# PCB1.net
KiCad netlist of a schematic drawn in Altium Designer
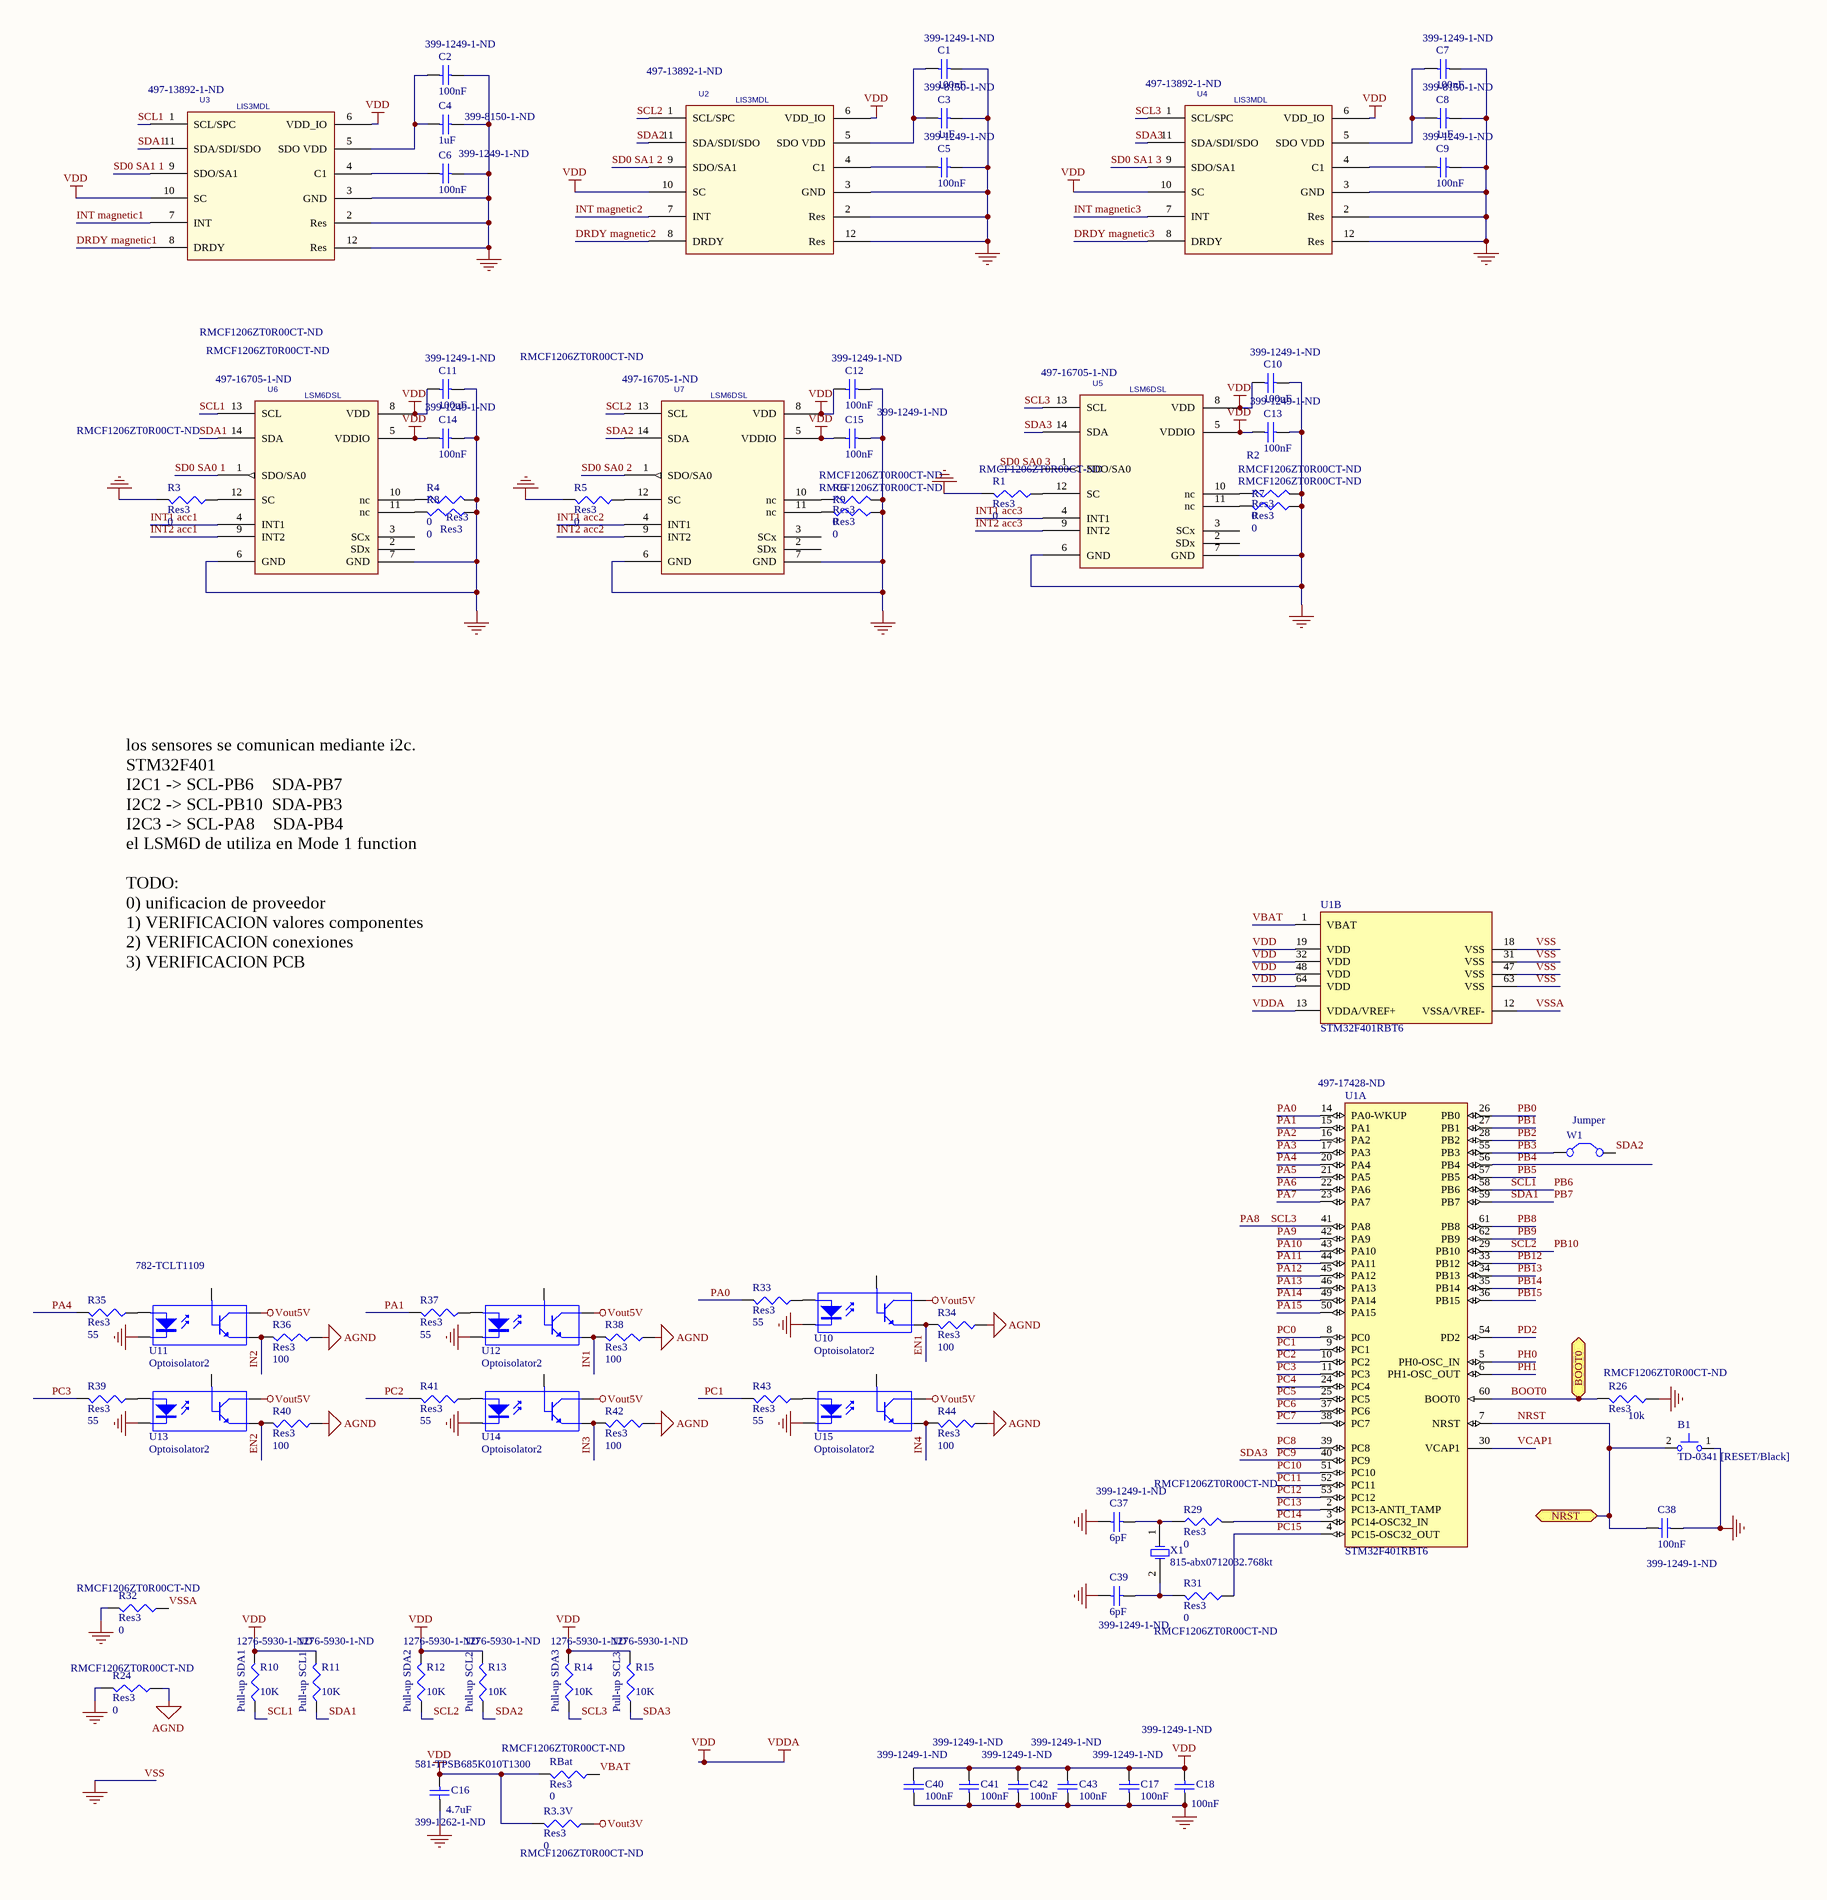
[diagram p0: PCB1.SchDoc, left]
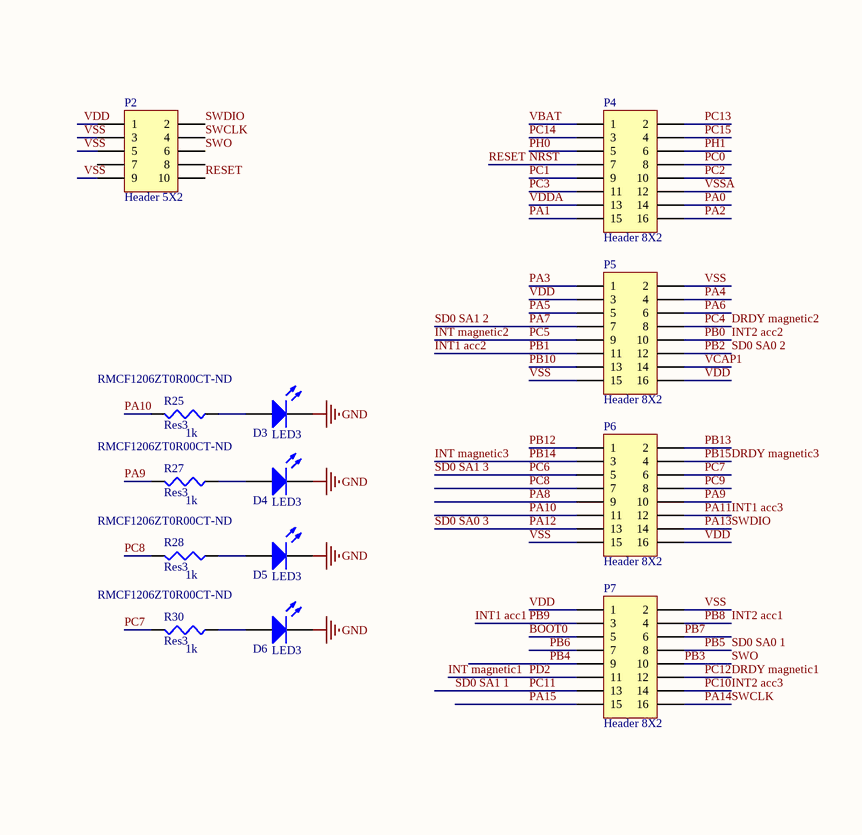
[diagram p1: PCB1.SchDoc, right]

(export (version "E")
  (design (tool "Eeschema 10.0.6"))
  (components
    (comp (ref "B1")
      (value "TD-0341 [RESET/Black]")
      (footprint "KSS-2G")
      (fields (field (name "PUBLISHER") "Altium Limited"))
      (libsource (lib "CK Switch") (part "KSS241GLFS"))
    )
    (comp (ref "C1")
      (value "100nF")
      (footprint "C1206")
      (description "Capacitor (Semiconductor SIM Model)")
      (fields
        (field (name "SUPPLIER PART NUMBER 1") "399-1249-1-ND")
        (field (name "Comment") "Cap Semi")
        (field (name "PUBLISHER") "Altium Limited")
      )
      (libsource (lib "Miscellaneous Devices") (part "Cap Semi"))
    )
    (comp (ref "C2")
      (value "100nF")
      (footprint "C1206")
      (description "Capacitor (Semiconductor SIM Model)")
      (fields
        (field (name "SUPPLIER PART NUMBER 1") "399-1249-1-ND")
        (field (name "Comment") "Cap Semi")
        (field (name "PUBLISHER") "Altium Limited")
      )
      (libsource (lib "Miscellaneous Devices") (part "Cap Semi"))
    )
    (comp (ref "C3")
      (value "1uF")
      (footprint "C1206")
      (description "Capacitor (Semiconductor SIM Model)")
      (fields
        (field (name "SUPPLIER PART NUMBER 1") "399-8150-1-ND")
        (field (name "Comment") "Cap Semi")
        (field (name "PUBLISHER") "Altium Limited")
      )
      (libsource (lib "Miscellaneous Devices") (part "Cap Semi"))
    )
    (comp (ref "C4")
      (value "1uF")
      (footprint "C1206")
      (description "Capacitor (Semiconductor SIM Model)")
      (fields
        (field (name "SUPPLIER PART NUMBER 1") "399-8150-1-ND")
        (field (name "Comment") "Cap Semi")
        (field (name "PUBLISHER") "Altium Limited")
      )
      (libsource (lib "Miscellaneous Devices") (part "Cap Semi"))
    )
    (comp (ref "C5")
      (value "100nF")
      (footprint "C1206")
      (description "Capacitor (Semiconductor SIM Model)")
      (fields
        (field (name "SUPPLIER PART NUMBER 1") "399-1249-1-ND")
        (field (name "Comment") "Cap Semi")
        (field (name "PUBLISHER") "Altium Limited")
      )
      (libsource (lib "Miscellaneous Devices") (part "Cap Semi"))
    )
    (comp (ref "C6")
      (value "100nF")
      (footprint "C1206")
      (description "Capacitor (Semiconductor SIM Model)")
      (fields
        (field (name "SUPPLIER PART NUMBER 1") "399-1249-1-ND")
        (field (name "Comment") "Cap Semi")
        (field (name "PUBLISHER") "Altium Limited")
      )
      (libsource (lib "Miscellaneous Devices") (part "Cap Semi"))
    )
    (comp (ref "C7")
      (value "100nF")
      (footprint "C1206")
      (description "Capacitor (Semiconductor SIM Model)")
      (fields
        (field (name "SUPPLIER PART NUMBER 1") "399-1249-1-ND")
        (field (name "Comment") "Cap Semi")
        (field (name "PUBLISHER") "Altium Limited")
      )
      (libsource (lib "Miscellaneous Devices") (part "Cap Semi"))
    )
    (comp (ref "C8")
      (value "1uF")
      (footprint "C1206")
      (description "Capacitor (Semiconductor SIM Model)")
      (fields
        (field (name "SUPPLIER PART NUMBER 1") "399-8150-1-ND")
        (field (name "Comment") "Cap Semi")
        (field (name "PUBLISHER") "Altium Limited")
      )
      (libsource (lib "Miscellaneous Devices") (part "Cap Semi"))
    )
    (comp (ref "C9")
      (value "100nF")
      (footprint "C1206")
      (description "Capacitor (Semiconductor SIM Model)")
      (fields
        (field (name "SUPPLIER PART NUMBER 1") "399-1249-1-ND")
        (field (name "Comment") "Cap Semi")
        (field (name "PUBLISHER") "Altium Limited")
      )
      (libsource (lib "Miscellaneous Devices") (part "Cap Semi"))
    )
    (comp (ref "C10")
      (value "100nF")
      (footprint "C1206")
      (description "Capacitor (Semiconductor SIM Model)")
      (fields
        (field (name "SUPPLIER PART NUMBER 1") "399-1249-1-ND")
        (field (name "Comment") "Cap Semi")
        (field (name "PUBLISHER") "Altium Limited")
      )
      (libsource (lib "Miscellaneous Devices") (part "Cap Semi"))
    )
    (comp (ref "C11")
      (value "100nF")
      (footprint "C1206")
      (description "Capacitor (Semiconductor SIM Model)")
      (fields
        (field (name "SUPPLIER PART NUMBER 1") "399-1249-1-ND")
        (field (name "Comment") "Cap Semi")
        (field (name "PUBLISHER") "Altium Limited")
      )
      (libsource (lib "Miscellaneous Devices") (part "Cap Semi"))
    )
    (comp (ref "C12")
      (value "100nF")
      (footprint "C1206")
      (description "Capacitor (Semiconductor SIM Model)")
      (fields
        (field (name "SUPPLIER PART NUMBER 1") "399-1249-1-ND")
        (field (name "Comment") "Cap Semi")
        (field (name "PUBLISHER") "Altium Limited")
      )
      (libsource (lib "Miscellaneous Devices") (part "Cap Semi"))
    )
    (comp (ref "C13")
      (value "100nF")
      (footprint "C1206")
      (description "Capacitor (Semiconductor SIM Model)")
      (fields
        (field (name "SUPPLIER PART NUMBER 1") "399-1249-1-ND")
        (field (name "Comment") "Cap Semi")
        (field (name "PUBLISHER") "Altium Limited")
      )
      (libsource (lib "Miscellaneous Devices") (part "Cap Semi"))
    )
    (comp (ref "C14")
      (value "100nF")
      (footprint "C1206")
      (description "Capacitor (Semiconductor SIM Model)")
      (fields
        (field (name "SUPPLIER PART NUMBER 1") "399-1249-1-ND")
        (field (name "Comment") "Cap Semi")
        (field (name "PUBLISHER") "Altium Limited")
      )
      (libsource (lib "Miscellaneous Devices") (part "Cap Semi"))
    )
    (comp (ref "C15")
      (value "100nF")
      (footprint "C1206")
      (description "Capacitor (Semiconductor SIM Model)")
      (fields
        (field (name "SUPPLIER PART NUMBER 1") "399-1249-1-ND")
        (field (name "Comment") "Cap Semi")
        (field (name "PUBLISHER") "Altium Limited")
      )
      (libsource (lib "Miscellaneous Devices") (part "Cap Semi"))
    )
    (comp (ref "C16")
      (value "4.7uF")
      (footprint "C1206")
      (description "Capacitor (Semiconductor SIM Model)")
      (fields
        (field (name "SUPPLIER PART NUMBER 1") "399-1262-1-ND")
        (field (name "SUPPLIER PART NUMBER 2") "581-TPSB685K010T1300")
        (field (name "Comment") "Cap Semi")
        (field (name "PUBLISHER") "Altium Limited")
      )
      (libsource (lib "Miscellaneous Devices") (part "Cap Semi"))
    )
    (comp (ref "C17")
      (value "100nF")
      (footprint "C1206")
      (description "Capacitor (Semiconductor SIM Model)")
      (fields
        (field (name "SUPPLIER PART NUMBER 1") "399-1249-1-ND")
        (field (name "Comment") "Cap Semi")
        (field (name "PUBLISHER") "Altium Limited")
      )
      (libsource (lib "Miscellaneous Devices") (part "Cap Semi"))
    )
    (comp (ref "C18")
      (value "100nF")
      (footprint "C1206")
      (description "Capacitor (Semiconductor SIM Model)")
      (fields
        (field (name "SUPPLIER PART NUMBER 1") "399-1249-1-ND")
        (field (name "Comment") "Cap Semi")
        (field (name "PUBLISHER") "Altium Limited")
      )
      (libsource (lib "Miscellaneous Devices") (part "Cap Semi"))
    )
    (comp (ref "C37")
      (value "6pF")
      (footprint "C1206")
      (description "Capacitor (Semiconductor SIM Model)")
      (fields
        (field (name "SUPPLIER PART NUMBER 1") "399-1249-1-ND")
        (field (name "Comment") "Cap Semi")
        (field (name "PUBLISHER") "Altium Limited")
      )
      (libsource (lib "Miscellaneous Devices") (part "Cap Semi"))
    )
    (comp (ref "C38")
      (value "100nF")
      (footprint "C1206")
      (description "Capacitor (Semiconductor SIM Model)")
      (fields
        (field (name "SUPPLIER PART NUMBER 1") "399-1249-1-ND")
        (field (name "Comment") "Cap Semi")
        (field (name "PUBLISHER") "Altium Limited")
      )
      (libsource (lib "Miscellaneous Devices") (part "Cap Semi"))
    )
    (comp (ref "C39")
      (value "6pF")
      (footprint "C1206")
      (description "Capacitor (Semiconductor SIM Model)")
      (fields
        (field (name "SUPPLIER PART NUMBER 1") "399-1249-1-ND")
        (field (name "Comment") "Cap Semi")
        (field (name "PUBLISHER") "Altium Limited")
      )
      (libsource (lib "Miscellaneous Devices") (part "Cap Semi"))
    )
    (comp (ref "C40")
      (value "100nF")
      (footprint "C1206")
      (description "Capacitor (Semiconductor SIM Model)")
      (fields
        (field (name "SUPPLIER PART NUMBER 1") "399-1249-1-ND")
        (field (name "Comment") "Cap Semi")
        (field (name "PUBLISHER") "Altium Limited")
      )
      (libsource (lib "Miscellaneous Devices") (part "Cap Semi"))
    )
    (comp (ref "C41")
      (value "100nF")
      (footprint "C1206")
      (description "Capacitor (Semiconductor SIM Model)")
      (fields
        (field (name "SUPPLIER PART NUMBER 1") "399-1249-1-ND")
        (field (name "Comment") "Cap Semi")
        (field (name "PUBLISHER") "Altium Limited")
      )
      (libsource (lib "Miscellaneous Devices") (part "Cap Semi"))
    )
    (comp (ref "C42")
      (value "100nF")
      (footprint "C1206")
      (description "Capacitor (Semiconductor SIM Model)")
      (fields
        (field (name "SUPPLIER PART NUMBER 1") "399-1249-1-ND")
        (field (name "Comment") "Cap Semi")
        (field (name "PUBLISHER") "Altium Limited")
      )
      (libsource (lib "Miscellaneous Devices") (part "Cap Semi"))
    )
    (comp (ref "C43")
      (value "100nF")
      (footprint "C1206")
      (description "Capacitor (Semiconductor SIM Model)")
      (fields
        (field (name "SUPPLIER PART NUMBER 1") "399-1249-1-ND")
        (field (name "Comment") "Cap Semi")
        (field (name "PUBLISHER") "Altium Limited")
      )
      (libsource (lib "Miscellaneous Devices") (part "Cap Semi"))
    )
    (comp (ref "D3")
      (value "LED3")
      (footprint "3.5X2.8X1.9")
      (description "Typical BLUE SiC LED")
      (fields (field (name "PUBLISHER") "Altium Limited"))
      (libsource (lib "Miscellaneous Devices") (part "LED3"))
    )
    (comp (ref "D4")
      (value "LED3")
      (footprint "3.5X2.8X1.9")
      (description "Typical BLUE SiC LED")
      (fields (field (name "PUBLISHER") "Altium Limited"))
      (libsource (lib "Miscellaneous Devices") (part "LED3"))
    )
    (comp (ref "D5")
      (value "LED3")
      (footprint "3.5X2.8X1.9")
      (description "Typical BLUE SiC LED")
      (fields (field (name "PUBLISHER") "Altium Limited"))
      (libsource (lib "Miscellaneous Devices") (part "LED3"))
    )
    (comp (ref "D6")
      (value "LED3")
      (footprint "3.5X2.8X1.9")
      (description "Typical BLUE SiC LED")
      (fields (field (name "PUBLISHER") "Altium Limited"))
      (libsource (lib "Miscellaneous Devices") (part "LED3"))
    )
    (comp (ref "P2")
      (value "Header 5X2")
      (footprint "HDR2X5")
      (description "Header, 5-Pin, Dual row")
      (fields (field (name "PUBLISHER") "Altium Limited"))
      (libsource (lib "Miscellaneous Connectors") (part "Header 5X2"))
    )
    (comp (ref "P4")
      (value "Header 8X2")
      (footprint "HDR2X8")
      (description "Header, 8-Pin, Dual row")
      (fields (field (name "PUBLISHER") "Altium Limited"))
      (libsource (lib "Miscellaneous Connectors") (part "Header 8X2"))
    )
    (comp (ref "P5")
      (value "Header 8X2")
      (footprint "HDR2X8")
      (description "Header, 8-Pin, Dual row")
      (fields (field (name "PUBLISHER") "Altium Limited"))
      (libsource (lib "Miscellaneous Connectors") (part "Header 8X2"))
    )
    (comp (ref "P6")
      (value "Header 8X2")
      (footprint "HDR2X8")
      (description "Header, 8-Pin, Dual row")
      (fields (field (name "PUBLISHER") "Altium Limited"))
      (libsource (lib "Miscellaneous Connectors") (part "Header 8X2"))
    )
    (comp (ref "P7")
      (value "Header 8X2")
      (footprint "HDR2X8")
      (description "Header, 8-Pin, Dual row")
      (fields (field (name "PUBLISHER") "Altium Limited"))
      (libsource (lib "Miscellaneous Connectors") (part "Header 8X2"))
    )
    (comp (ref "R1")
      (value "Res3")
      (footprint "J1-0603")
      (description "Resistor")
      (fields
        (field (name "ALTIUM_VALUE") "0")
        (field (name "SUPPLIER PART NUMBER 1") "RMCF1206ZT0R00CT-ND")
        (field (name "PUBLISHER") "Altium Limited")
      )
      (libsource (lib "Miscellaneous Devices") (part "Res3"))
    )
    (comp (ref "R2")
      (value "Res3")
      (footprint "J1-0603")
      (description "Resistor")
      (fields
        (field (name "ALTIUM_VALUE") "0")
        (field (name "SUPPLIER PART NUMBER 1") "RMCF1206ZT0R00CT-ND")
        (field (name "PUBLISHER") "Altium Limited")
      )
      (libsource (lib "Miscellaneous Devices") (part "Res3"))
    )
    (comp (ref "R3")
      (value "Res3")
      (footprint "J1-0603")
      (description "Resistor")
      (fields
        (field (name "ALTIUM_VALUE") "0")
        (field (name "SUPPLIER PART NUMBER 1") "RMCF1206ZT0R00CT-ND")
        (field (name "PUBLISHER") "Altium Limited")
      )
      (libsource (lib "Miscellaneous Devices") (part "Res3"))
    )
    (comp (ref "R3.3V")
      (value "Res3")
      (footprint "J1-0603")
      (description "Resistor")
      (fields
        (field (name "ALTIUM_VALUE") "0")
        (field (name "SUPPLIER PART NUMBER 1") "RMCF1206ZT0R00CT-ND")
        (field (name "PUBLISHER") "Altium Limited")
      )
      (libsource (lib "Miscellaneous Devices") (part "Res3"))
    )
    (comp (ref "R4")
      (value "Res3")
      (footprint "J1-0603")
      (description "Resistor")
      (fields
        (field (name "ALTIUM_VALUE") "0")
        (field (name "SUPPLIER PART NUMBER 1") "RMCF1206ZT0R00CT-ND")
        (field (name "PUBLISHER") "Altium Limited")
      )
      (libsource (lib "Miscellaneous Devices") (part "Res3"))
    )
    (comp (ref "R5")
      (value "Res3")
      (footprint "J1-0603")
      (description "Resistor")
      (fields
        (field (name "ALTIUM_VALUE") "0")
        (field (name "SUPPLIER PART NUMBER 1") "RMCF1206ZT0R00CT-ND")
        (field (name "PUBLISHER") "Altium Limited")
      )
      (libsource (lib "Miscellaneous Devices") (part "Res3"))
    )
    (comp (ref "R6")
      (value "Res3")
      (footprint "J1-0603")
      (description "Resistor")
      (fields
        (field (name "ALTIUM_VALUE") "0")
        (field (name "SUPPLIER PART NUMBER 1") "RMCF1206ZT0R00CT-ND")
        (field (name "PUBLISHER") "Altium Limited")
      )
      (libsource (lib "Miscellaneous Devices") (part "Res3"))
    )
    (comp (ref "R7")
      (value "Res3")
      (footprint "J1-0603")
      (description "Resistor")
      (fields
        (field (name "ALTIUM_VALUE") "0")
        (field (name "SUPPLIER PART NUMBER 1") "RMCF1206ZT0R00CT-ND")
        (field (name "PUBLISHER") "Altium Limited")
      )
      (libsource (lib "Miscellaneous Devices") (part "Res3"))
    )
    (comp (ref "R8")
      (value "Res3")
      (footprint "J1-0603")
      (description "Resistor")
      (fields
        (field (name "ALTIUM_VALUE") "0")
        (field (name "SUPPLIER PART NUMBER 1") "RMCF1206ZT0R00CT-ND")
        (field (name "PUBLISHER") "Altium Limited")
      )
      (libsource (lib "Miscellaneous Devices") (part "Res3"))
    )
    (comp (ref "R9")
      (value "Res3")
      (footprint "J1-0603")
      (description "Resistor")
      (fields
        (field (name "ALTIUM_VALUE") "0")
        (field (name "SUPPLIER PART NUMBER 1") "RMCF1206ZT0R00CT-ND")
        (field (name "PUBLISHER") "Altium Limited")
      )
      (libsource (lib "Miscellaneous Devices") (part "Res3"))
    )
    (comp (ref "R10")
      (value "Pull-up SDA1")
      (footprint "J1-0603")
      (description "Resistor")
      (fields
        (field (name "ALTIUM_VALUE") "10K")
        (field (name "SUPPLIER PART NUMBER 1") "1276-5930-1-ND")
        (field (name "PUBLISHER") "Altium Limited")
      )
      (libsource (lib "Miscellaneous Devices") (part "Res3"))
    )
    (comp (ref "R11")
      (value "Pull-up SCL1")
      (footprint "J1-0603")
      (description "Resistor")
      (fields
        (field (name "ALTIUM_VALUE") "10K")
        (field (name "SUPPLIER PART NUMBER 1") "1276-5930-1-ND")
        (field (name "PUBLISHER") "Altium Limited")
      )
      (libsource (lib "Miscellaneous Devices") (part "Res3"))
    )
    (comp (ref "R12")
      (value "Pull-up SDA2")
      (footprint "J1-0603")
      (description "Resistor")
      (fields
        (field (name "ALTIUM_VALUE") "10K")
        (field (name "SUPPLIER PART NUMBER 1") "1276-5930-1-ND")
        (field (name "PUBLISHER") "Altium Limited")
      )
      (libsource (lib "Miscellaneous Devices") (part "Res3"))
    )
    (comp (ref "R13")
      (value "Pull-up SCL2")
      (footprint "J1-0603")
      (description "Resistor")
      (fields
        (field (name "ALTIUM_VALUE") "10K")
        (field (name "SUPPLIER PART NUMBER 1") "1276-5930-1-ND")
        (field (name "PUBLISHER") "Altium Limited")
      )
      (libsource (lib "Miscellaneous Devices") (part "Res3"))
    )
    (comp (ref "R14")
      (value "Pull-up SDA3")
      (footprint "J1-0603")
      (description "Resistor")
      (fields
        (field (name "ALTIUM_VALUE") "10K")
        (field (name "SUPPLIER PART NUMBER 1") "1276-5930-1-ND")
        (field (name "PUBLISHER") "Altium Limited")
      )
      (libsource (lib "Miscellaneous Devices") (part "Res3"))
    )
    (comp (ref "R15")
      (value "Pull-up SCL3")
      (footprint "J1-0603")
      (description "Resistor")
      (fields
        (field (name "ALTIUM_VALUE") "10K")
        (field (name "SUPPLIER PART NUMBER 1") "1276-5930-1-ND")
        (field (name "PUBLISHER") "Altium Limited")
      )
      (libsource (lib "Miscellaneous Devices") (part "Res3"))
    )
    (comp (ref "R24")
      (value "Res3")
      (footprint "J1-0603")
      (description "Resistor")
      (fields
        (field (name "ALTIUM_VALUE") "0")
        (field (name "SUPPLIER PART NUMBER 1") "RMCF1206ZT0R00CT-ND")
        (field (name "PUBLISHER") "Altium Limited")
      )
      (libsource (lib "Miscellaneous Devices") (part "Res3"))
    )
    (comp (ref "R25")
      (value "Res3")
      (footprint "J1-0603")
      (description "Resistor")
      (fields
        (field (name "ALTIUM_VALUE") "1k")
        (field (name "SUPPLIER PART NUMBER 1") "RMCF1206ZT0R00CT-ND")
        (field (name "PUBLISHER") "Altium Limited")
      )
      (libsource (lib "Miscellaneous Devices") (part "Res3"))
    )
    (comp (ref "R26")
      (value "Res3")
      (footprint "J1-0603")
      (description "Resistor")
      (fields
        (field (name "ALTIUM_VALUE") "10k")
        (field (name "SUPPLIER PART NUMBER 1") "RMCF1206ZT0R00CT-ND")
        (field (name "PUBLISHER") "Altium Limited")
      )
      (libsource (lib "Miscellaneous Devices") (part "Res3"))
    )
    (comp (ref "R27")
      (value "Res3")
      (footprint "J1-0603")
      (description "Resistor")
      (fields
        (field (name "ALTIUM_VALUE") "1k")
        (field (name "SUPPLIER PART NUMBER 1") "RMCF1206ZT0R00CT-ND")
        (field (name "PUBLISHER") "Altium Limited")
      )
      (libsource (lib "Miscellaneous Devices") (part "Res3"))
    )
    (comp (ref "R28")
      (value "Res3")
      (footprint "J1-0603")
      (description "Resistor")
      (fields
        (field (name "ALTIUM_VALUE") "1k")
        (field (name "SUPPLIER PART NUMBER 1") "RMCF1206ZT0R00CT-ND")
        (field (name "PUBLISHER") "Altium Limited")
      )
      (libsource (lib "Miscellaneous Devices") (part "Res3"))
    )
    (comp (ref "R29")
      (value "Res3")
      (footprint "J1-0603")
      (description "Resistor")
      (fields
        (field (name "ALTIUM_VALUE") "0")
        (field (name "SUPPLIER PART NUMBER 1") "RMCF1206ZT0R00CT-ND")
        (field (name "PUBLISHER") "Altium Limited")
      )
      (libsource (lib "Miscellaneous Devices") (part "Res3"))
    )
    (comp (ref "R30")
      (value "Res3")
      (footprint "J1-0603")
      (description "Resistor")
      (fields
        (field (name "ALTIUM_VALUE") "1k")
        (field (name "SUPPLIER PART NUMBER 1") "RMCF1206ZT0R00CT-ND")
        (field (name "PUBLISHER") "Altium Limited")
      )
      (libsource (lib "Miscellaneous Devices") (part "Res3"))
    )
    (comp (ref "R31")
      (value "Res3")
      (footprint "J1-0603")
      (description "Resistor")
      (fields
        (field (name "ALTIUM_VALUE") "0")
        (field (name "SUPPLIER PART NUMBER 1") "RMCF1206ZT0R00CT-ND")
        (field (name "PUBLISHER") "Altium Limited")
      )
      (libsource (lib "Miscellaneous Devices") (part "Res3"))
    )
    (comp (ref "R32")
      (value "Res3")
      (footprint "J1-0603")
      (description "Resistor")
      (fields
        (field (name "ALTIUM_VALUE") "0")
        (field (name "SUPPLIER PART NUMBER 1") "RMCF1206ZT0R00CT-ND")
        (field (name "PUBLISHER") "Altium Limited")
      )
      (libsource (lib "Miscellaneous Devices") (part "Res3"))
    )
    (comp (ref "R33")
      (value "Res3")
      (footprint "J1-0603")
      (description "Resistor")
      (fields (field (name "ALTIUM_VALUE") "55") (field (name "PUBLISHER") "Altium Limited"))
      (libsource (lib "Miscellaneous Devices") (part "Res3"))
    )
    (comp (ref "R34")
      (value "Res3")
      (footprint "J1-0603")
      (description "Resistor")
      (fields (field (name "ALTIUM_VALUE") "100") (field (name "PUBLISHER") "Altium Limited"))
      (libsource (lib "Miscellaneous Devices") (part "Res3"))
    )
    (comp (ref "R35")
      (value "Res3")
      (footprint "J1-0603")
      (description "Resistor")
      (fields (field (name "ALTIUM_VALUE") "55") (field (name "PUBLISHER") "Altium Limited"))
      (libsource (lib "Miscellaneous Devices") (part "Res3"))
    )
    (comp (ref "R36")
      (value "Res3")
      (footprint "J1-0603")
      (description "Resistor")
      (fields (field (name "ALTIUM_VALUE") "100") (field (name "PUBLISHER") "Altium Limited"))
      (libsource (lib "Miscellaneous Devices") (part "Res3"))
    )
    (comp (ref "R37")
      (value "Res3")
      (footprint "J1-0603")
      (description "Resistor")
      (fields (field (name "ALTIUM_VALUE") "55") (field (name "PUBLISHER") "Altium Limited"))
      (libsource (lib "Miscellaneous Devices") (part "Res3"))
    )
    (comp (ref "R38")
      (value "Res3")
      (footprint "J1-0603")
      (description "Resistor")
      (fields (field (name "ALTIUM_VALUE") "100") (field (name "PUBLISHER") "Altium Limited"))
      (libsource (lib "Miscellaneous Devices") (part "Res3"))
    )
    (comp (ref "R39")
      (value "Res3")
      (footprint "J1-0603")
      (description "Resistor")
      (fields (field (name "ALTIUM_VALUE") "55") (field (name "PUBLISHER") "Altium Limited"))
      (libsource (lib "Miscellaneous Devices") (part "Res3"))
    )
    (comp (ref "R40")
      (value "Res3")
      (footprint "J1-0603")
      (description "Resistor")
      (fields (field (name "ALTIUM_VALUE") "100") (field (name "PUBLISHER") "Altium Limited"))
      (libsource (lib "Miscellaneous Devices") (part "Res3"))
    )
    (comp (ref "R41")
      (value "Res3")
      (footprint "J1-0603")
      (description "Resistor")
      (fields (field (name "ALTIUM_VALUE") "55") (field (name "PUBLISHER") "Altium Limited"))
      (libsource (lib "Miscellaneous Devices") (part "Res3"))
    )
    (comp (ref "R42")
      (value "Res3")
      (footprint "J1-0603")
      (description "Resistor")
      (fields (field (name "ALTIUM_VALUE") "100") (field (name "PUBLISHER") "Altium Limited"))
      (libsource (lib "Miscellaneous Devices") (part "Res3"))
    )
    (comp (ref "R43")
      (value "Res3")
      (footprint "J1-0603")
      (description "Resistor")
      (fields (field (name "ALTIUM_VALUE") "55") (field (name "PUBLISHER") "Altium Limited"))
      (libsource (lib "Miscellaneous Devices") (part "Res3"))
    )
    (comp (ref "R44")
      (value "Res3")
      (footprint "J1-0603")
      (description "Resistor")
      (fields (field (name "ALTIUM_VALUE") "100") (field (name "PUBLISHER") "Altium Limited"))
      (libsource (lib "Miscellaneous Devices") (part "Res3"))
    )
    (comp (ref "RBat")
      (value "Res3")
      (footprint "J1-0603")
      (description "Resistor")
      (fields
        (field (name "ALTIUM_VALUE") "0")
        (field (name "SUPPLIER PART NUMBER 1") "RMCF1206ZT0R00CT-ND")
        (field (name "PUBLISHER") "Altium Limited")
      )
      (libsource (lib "Miscellaneous Devices") (part "Res3"))
    )
    (comp (ref "U1")
      (value "STM32F401RBT6")
      (footprint "STM-LQFP64_N")
      (fields
        (field (name "MANUFACTURER") "STMicroelectronics")
        (field (name "SUPPLIER PART NUMBER 3") "497-17428-ND")
      )
      (libsource (lib "STMicroelectronics STM32 F4") (part "STM32F401RBT6"))
    )
    (comp (ref "U2")
      (value "LIS3MDL")
      (footprint "LGA12 2x2x1mm")
      (description "Magnetic sensor MEMS (3 Axis)")
      (fields (field (name "SUPPLIER PART NUMBER 1") "497-13892-1-ND"))
      (libsource (lib "Open_Parts_Library_Altium") (part "LIS3MDL"))
    )
    (comp (ref "U3")
      (value "LIS3MDL")
      (footprint "LGA12 2x2x1mm")
      (description "Magnetic sensor MEMS (3 Axis)")
      (fields (field (name "SUPPLIER PART NUMBER 1") "497-13892-1-ND"))
      (libsource (lib "Open_Parts_Library_Altium") (part "LIS3MDL"))
    )
    (comp (ref "U4")
      (value "LIS3MDL")
      (footprint "LGA12 2x2x1mm")
      (description "Magnetic sensor MEMS (3 Axis)")
      (fields (field (name "SUPPLIER PART NUMBER 1") "497-13892-1-ND"))
      (libsource (lib "Open_Parts_Library_Altium") (part "LIS3MDL"))
    )
    (comp (ref "U5")
      (value "LSM6DSL")
      (footprint "LGA14L-2.5X3X0.86p0.5")
      (description "Accelero + Gyro MEMS (6 Axis)")
      (fields (field (name "SUPPLIER PART NUMBER 1") "497-16705-1-ND"))
      (libsource (lib "Open_Parts_Library_Altium") (part "LSM6DSL"))
    )
    (comp (ref "U6")
      (value "LSM6DSL")
      (footprint "LGA14L-2.5X3X0.86p0.5")
      (description "Accelero + Gyro MEMS (6 Axis)")
      (fields (field (name "SUPPLIER PART NUMBER 1") "497-16705-1-ND"))
      (libsource (lib "Open_Parts_Library_Altium") (part "LSM6DSL"))
    )
    (comp (ref "U7")
      (value "LSM6DSL")
      (footprint "LGA14L-2.5X3X0.86p0.5")
      (description "Accelero + Gyro MEMS (6 Axis)")
      (fields (field (name "SUPPLIER PART NUMBER 1") "497-16705-1-ND"))
      (libsource (lib "Open_Parts_Library_Altium") (part "LSM6DSL"))
    )
    (comp (ref "U10")
      (value "Optoisolator2")
      (footprint "SOP5(6)")
      (description "5 Pin Mini Flat Pack Optocoupler")
      (fields (field (name "PUBLISHER") "Altium Limited"))
      (libsource (lib "Miscellaneous Devices") (part "Optoisolator2"))
    )
    (comp (ref "U11")
      (value "Optoisolator2")
      (footprint "SOP5(6)")
      (description "5 Pin Mini Flat Pack Optocoupler")
      (fields
        (field (name "SUPPLIER PART NUMBER 1") "782-TCLT1109")
        (field (name "PUBLISHER") "Altium Limited")
      )
      (libsource (lib "Miscellaneous Devices") (part "Optoisolator2"))
    )
    (comp (ref "U12")
      (value "Optoisolator2")
      (footprint "SOP5(6)")
      (description "5 Pin Mini Flat Pack Optocoupler")
      (fields (field (name "PUBLISHER") "Altium Limited"))
      (libsource (lib "Miscellaneous Devices") (part "Optoisolator2"))
    )
    (comp (ref "U13")
      (value "Optoisolator2")
      (footprint "SOP5(6)")
      (description "5 Pin Mini Flat Pack Optocoupler")
      (fields (field (name "PUBLISHER") "Altium Limited"))
      (libsource (lib "Miscellaneous Devices") (part "Optoisolator2"))
    )
    (comp (ref "U14")
      (value "Optoisolator2")
      (footprint "SOP5(6)")
      (description "5 Pin Mini Flat Pack Optocoupler")
      (fields (field (name "PUBLISHER") "Altium Limited"))
      (libsource (lib "Miscellaneous Devices") (part "Optoisolator2"))
    )
    (comp (ref "U15")
      (value "Optoisolator2")
      (footprint "SOP5(6)")
      (description "5 Pin Mini Flat Pack Optocoupler")
      (fields (field (name "PUBLISHER") "Altium Limited"))
      (libsource (lib "Miscellaneous Devices") (part "Optoisolator2"))
    )
    (comp (ref "W1")
      (value "Jumper")
      (footprint "HDR1X2")
      (description "Jumper Wire")
      (fields (field (name "PUBLISHER") "Altium Limited"))
      (libsource (lib "Miscellaneous Devices") (part "Jumper"))
    )
    (comp (ref "X1")
      (value "815-abx0712032.768kt")
      (footprint "CAPC3216M")
      (description "Crystal Oscillator")
      (fields (field (name "PUBLISHER") "Altium Limited"))
      (libsource (lib "Miscellaneous Devices") (part "XTAL"))
    )
  )
  (nets
    (net (code "1") (name "/BOOT0") (class "Default")
      (node (ref "P7") (pin "5") (pinfunction "5_5") (pintype "passive"))
      (node (ref "R26") (pin "2") (pinfunction "2_2") (pintype "passive"))
      (node (ref "U1") (pin "60") (pinfunction "BOOT0_60") (pintype "input"))
    )
    (net (code "2") (name "/DRDY magnetic1") (class "Default")
      (node (ref "P7") (pin "12") (pinfunction "12_12") (pintype "passive"))
      (node (ref "U1") (pin "53") (pinfunction "PC12_53") (pintype "bidirectional"))
      (node (ref "U3") (pin "8") (pinfunction "DRDY_8") (pintype "passive"))
    )
    (net (code "3") (name "/DRDY magnetic2") (class "Default")
      (node (ref "P5") (pin "8") (pinfunction "8_8") (pintype "passive"))
      (node (ref "U1") (pin "24") (pinfunction "PC4_24") (pintype "bidirectional"))
      (node (ref "U2") (pin "8") (pinfunction "DRDY_8") (pintype "passive"))
    )
    (net (code "4") (name "/DRDY magnetic3") (class "Default")
      (node (ref "P6") (pin "4") (pinfunction "4_4") (pintype "passive"))
      (node (ref "U1") (pin "36") (pinfunction "PB15_36") (pintype "bidirectional"))
      (node (ref "U4") (pin "8") (pinfunction "DRDY_8") (pintype "passive"))
    )
    (net (code "5") (name "/EN1") (class "Default")
      (node (ref "R34") (pin "2") (pinfunction "2_2") (pintype "passive"))
      (node (ref "U10") (pin "4") (pinfunction "E_4") (pintype "passive"))
    )
    (net (code "6") (name "/EN2") (class "Default")
      (node (ref "R40") (pin "2") (pinfunction "2_2") (pintype "passive"))
      (node (ref "U13") (pin "4") (pinfunction "E_4") (pintype "passive"))
    )
    (net (code "7") (name "/IN1") (class "Default")
      (node (ref "R38") (pin "2") (pinfunction "2_2") (pintype "passive"))
      (node (ref "U12") (pin "4") (pinfunction "E_4") (pintype "passive"))
    )
    (net (code "8") (name "/IN2") (class "Default")
      (node (ref "R36") (pin "2") (pinfunction "2_2") (pintype "passive"))
      (node (ref "U11") (pin "4") (pinfunction "E_4") (pintype "passive"))
    )
    (net (code "9") (name "/IN3") (class "Default")
      (node (ref "R42") (pin "2") (pinfunction "2_2") (pintype "passive"))
      (node (ref "U14") (pin "4") (pinfunction "E_4") (pintype "passive"))
    )
    (net (code "10") (name "/IN4") (class "Default")
      (node (ref "R44") (pin "2") (pinfunction "2_2") (pintype "passive"))
      (node (ref "U15") (pin "4") (pinfunction "E_4") (pintype "passive"))
    )
    (net (code "11") (name "/INT magnetic1") (class "Default")
      (node (ref "P7") (pin "11") (pinfunction "11_11") (pintype "passive"))
      (node (ref "U1") (pin "54") (pinfunction "PD2_54") (pintype "bidirectional"))
      (node (ref "U3") (pin "7") (pinfunction "INT_7") (pintype "passive"))
    )
    (net (code "12") (name "/INT magnetic2") (class "Default")
      (node (ref "P5") (pin "9") (pinfunction "9_9") (pintype "passive"))
      (node (ref "U1") (pin "25") (pinfunction "PC5_25") (pintype "bidirectional"))
      (node (ref "U2") (pin "7") (pinfunction "INT_7") (pintype "passive"))
    )
    (net (code "13") (name "/INT magnetic3") (class "Default")
      (node (ref "P6") (pin "3") (pinfunction "3_3") (pintype "passive"))
      (node (ref "U1") (pin "35") (pinfunction "PB14_35") (pintype "bidirectional"))
      (node (ref "U4") (pin "7") (pinfunction "INT_7") (pintype "passive"))
    )
    (net (code "14") (name "/INT1 acc1") (class "Default")
      (node (ref "P7") (pin "3") (pinfunction "3_3") (pintype "passive"))
      (node (ref "U1") (pin "62") (pinfunction "PB9_62") (pintype "bidirectional"))
      (node (ref "U6") (pin "4") (pinfunction "INT1_4") (pintype "passive"))
    )
    (net (code "15") (name "/INT1 acc2") (class "Default")
      (node (ref "P5") (pin "11") (pinfunction "11_11") (pintype "passive"))
      (node (ref "U1") (pin "27") (pinfunction "PB1_27") (pintype "bidirectional"))
      (node (ref "U7") (pin "4") (pinfunction "INT1_4") (pintype "passive"))
    )
    (net (code "16") (name "/INT1 acc3") (class "Default")
      (node (ref "P6") (pin "12") (pinfunction "12_12") (pintype "passive"))
      (node (ref "U1") (pin "44") (pinfunction "PA11_44") (pintype "bidirectional"))
      (node (ref "U5") (pin "4") (pinfunction "INT1_4") (pintype "passive"))
    )
    (net (code "17") (name "/INT2 acc1") (class "Default")
      (node (ref "P7") (pin "4") (pinfunction "4_4") (pintype "passive"))
      (node (ref "U1") (pin "61") (pinfunction "PB8_61") (pintype "bidirectional"))
      (node (ref "U6") (pin "9") (pinfunction "INT2_9") (pintype "passive"))
    )
    (net (code "18") (name "/INT2 acc2") (class "Default")
      (node (ref "P5") (pin "10") (pinfunction "10_10") (pintype "passive"))
      (node (ref "U1") (pin "26") (pinfunction "PB0_26") (pintype "bidirectional"))
      (node (ref "U7") (pin "9") (pinfunction "INT2_9") (pintype "passive"))
    )
    (net (code "19") (name "/INT2 acc3") (class "Default")
      (node (ref "P7") (pin "14") (pinfunction "14_14") (pintype "passive"))
      (node (ref "U1") (pin "51") (pinfunction "PC10_51") (pintype "bidirectional"))
      (node (ref "U5") (pin "9") (pinfunction "INT2_9") (pintype "passive"))
    )
    (net (code "20") (name "/NRST") (class "Default")
      (node (ref "B1") (pin "2") (pinfunction "2_2") (pintype "passive"))
      (node (ref "C38") (pin "2") (pinfunction "2_2") (pintype "passive"))
      (node (ref "P2") (pin "10") (pinfunction "10_10") (pintype "passive"))
      (node (ref "P4") (pin "7") (pinfunction "7_7") (pintype "passive"))
      (node (ref "U1") (pin "7") (pinfunction "NRST_7") (pintype "bidirectional"))
    )
    (net (code "21") (name "/PA0") (class "Default")
      (node (ref "P4") (pin "14") (pinfunction "14_14") (pintype "passive"))
      (node (ref "R33") (pin "2") (pinfunction "2_2") (pintype "passive"))
      (node (ref "U1") (pin "14") (pinfunction "PA0-WKUP_14") (pintype "bidirectional"))
    )
    (net (code "22") (name "/PA1") (class "Default")
      (node (ref "P4") (pin "15") (pinfunction "15_15") (pintype "passive"))
      (node (ref "R37") (pin "2") (pinfunction "2_2") (pintype "passive"))
      (node (ref "U1") (pin "15") (pinfunction "PA1_15") (pintype "bidirectional"))
    )
    (net (code "23") (name "/PA2") (class "Default")
      (node (ref "P4") (pin "16") (pinfunction "16_16") (pintype "passive"))
      (node (ref "U1") (pin "16") (pinfunction "PA2_16") (pintype "bidirectional"))
    )
    (net (code "24") (name "/PA3") (class "Default")
      (node (ref "P5") (pin "1") (pinfunction "1_1") (pintype "passive"))
      (node (ref "U1") (pin "17") (pinfunction "PA3_17") (pintype "bidirectional"))
    )
    (net (code "25") (name "/PA4") (class "Default")
      (node (ref "P5") (pin "4") (pinfunction "4_4") (pintype "passive"))
      (node (ref "R35") (pin "2") (pinfunction "2_2") (pintype "passive"))
      (node (ref "U1") (pin "20") (pinfunction "PA4_20") (pintype "bidirectional"))
    )
    (net (code "26") (name "/PA5") (class "Default")
      (node (ref "P5") (pin "5") (pinfunction "5_5") (pintype "passive"))
      (node (ref "U1") (pin "21") (pinfunction "PA5_21") (pintype "bidirectional"))
    )
    (net (code "27") (name "/PA6") (class "Default")
      (node (ref "P5") (pin "6") (pinfunction "6_6") (pintype "passive"))
      (node (ref "U1") (pin "22") (pinfunction "PA6_22") (pintype "bidirectional"))
    )
    (net (code "28") (name "/PA7") (class "Default")
      (node (ref "P5") (pin "7") (pinfunction "7_7") (pintype "passive"))
      (node (ref "U1") (pin "23") (pinfunction "PA7_23") (pintype "bidirectional"))
      (node (ref "U2") (pin "9") (pinfunction "SDO/SA1_9") (pintype "passive"))
    )
    (net (code "29") (name "/PA8") (class "Default")
      (node (ref "P6") (pin "9") (pinfunction "9_9") (pintype "passive"))
      (node (ref "R14") (pin "1") (pinfunction "1_1") (pintype "passive"))
      (node (ref "U1") (pin "41") (pinfunction "PA8_41") (pintype "bidirectional"))
      (node (ref "U4") (pin "1") (pinfunction "SCL/SPC_1") (pintype "passive"))
      (node (ref "U5") (pin "13") (pinfunction "SCL_13") (pintype "passive"))
    )
    (net (code "30") (name "/PA9") (class "Default")
      (node (ref "P6") (pin "10") (pinfunction "10_10") (pintype "passive"))
      (node (ref "R27") (pin "2") (pinfunction "2_2") (pintype "passive"))
      (node (ref "U1") (pin "42") (pinfunction "PA9_42") (pintype "bidirectional"))
    )
    (net (code "31") (name "/PA10") (class "Default")
      (node (ref "P6") (pin "11") (pinfunction "11_11") (pintype "passive"))
      (node (ref "R25") (pin "2") (pinfunction "2_2") (pintype "passive"))
      (node (ref "U1") (pin "43") (pinfunction "PA10_43") (pintype "bidirectional"))
    )
    (net (code "32") (name "/PA12") (class "Default")
      (node (ref "P6") (pin "13") (pinfunction "13_13") (pintype "passive"))
      (node (ref "U1") (pin "45") (pinfunction "PA12_45") (pintype "bidirectional"))
      (node (ref "U5") (pin "1") (pinfunction "SDO/SA0_1") (pintype "output"))
    )
    (net (code "33") (name "/PA13") (class "Default")
      (node (ref "P2") (pin "2") (pinfunction "2_2") (pintype "passive"))
      (node (ref "P6") (pin "14") (pinfunction "14_14") (pintype "passive"))
      (node (ref "U1") (pin "46") (pinfunction "PA13_46") (pintype "bidirectional"))
    )
    (net (code "34") (name "/PA14") (class "Default")
      (node (ref "P2") (pin "4") (pinfunction "4_4") (pintype "passive"))
      (node (ref "P7") (pin "16") (pinfunction "16_16") (pintype "passive"))
      (node (ref "U1") (pin "49") (pinfunction "PA14_49") (pintype "bidirectional"))
    )
    (net (code "35") (name "/PA15") (class "Default")
      (node (ref "P7") (pin "15") (pinfunction "15_15") (pintype "passive"))
      (node (ref "U1") (pin "50") (pinfunction "PA15_50") (pintype "bidirectional"))
    )
    (net (code "36") (name "/PB2") (class "Default")
      (node (ref "P5") (pin "12") (pinfunction "12_12") (pintype "passive"))
      (node (ref "U1") (pin "28") (pinfunction "PB2_28") (pintype "bidirectional"))
      (node (ref "U7") (pin "1") (pinfunction "SDO/SA0_1") (pintype "output"))
    )
    (net (code "37") (name "/PB3") (class "Default")
      (node (ref "P2") (pin "6") (pinfunction "6_6") (pintype "passive"))
      (node (ref "P7") (pin "10") (pinfunction "10_10") (pintype "passive"))
      (node (ref "U1") (pin "55") (pinfunction "PB3_55") (pintype "bidirectional"))
      (node (ref "W1") (pin "1") (pinfunction "C1_1") (pintype "passive"))
    )
    (net (code "38") (name "/PB4") (class "Default")
      (node (ref "P7") (pin "9") (pinfunction "9_9") (pintype "passive"))
      (node (ref "U1") (pin "56") (pinfunction "PB4_56") (pintype "bidirectional"))
    )
    (net (code "39") (name "/PB5") (class "Default")
      (node (ref "P7") (pin "8") (pinfunction "8_8") (pintype "passive"))
      (node (ref "U1") (pin "57") (pinfunction "PB5_57") (pintype "bidirectional"))
      (node (ref "U6") (pin "1") (pinfunction "SDO/SA0_1") (pintype "output"))
    )
    (net (code "40") (name "/PB6") (class "Default")
      (node (ref "P7") (pin "7") (pinfunction "7_7") (pintype "passive"))
      (node (ref "R10") (pin "1") (pinfunction "1_1") (pintype "passive"))
      (node (ref "U1") (pin "58") (pinfunction "PB6_58") (pintype "bidirectional"))
      (node (ref "U3") (pin "1") (pinfunction "SCL/SPC_1") (pintype "passive"))
      (node (ref "U6") (pin "13") (pinfunction "SCL_13") (pintype "passive"))
    )
    (net (code "41") (name "/PB7") (class "Default")
      (node (ref "P7") (pin "6") (pinfunction "6_6") (pintype "passive"))
      (node (ref "R11") (pin "1") (pinfunction "1_1") (pintype "passive"))
      (node (ref "U1") (pin "59") (pinfunction "PB7_59") (pintype "bidirectional"))
      (node (ref "U3") (pin "11") (pinfunction "SDA/SDI/SDO_11") (pintype "passive"))
      (node (ref "U6") (pin "14") (pinfunction "SDA_14") (pintype "passive"))
    )
    (net (code "42") (name "/PB10") (class "Default")
      (node (ref "P5") (pin "13") (pinfunction "13_13") (pintype "passive"))
      (node (ref "R12") (pin "1") (pinfunction "1_1") (pintype "passive"))
      (node (ref "U1") (pin "29") (pinfunction "PB10_29") (pintype "bidirectional"))
      (node (ref "U2") (pin "1") (pinfunction "SCL/SPC_1") (pintype "passive"))
      (node (ref "U7") (pin "13") (pinfunction "SCL_13") (pintype "passive"))
    )
    (net (code "43") (name "/PB12") (class "Default")
      (node (ref "P6") (pin "1") (pinfunction "1_1") (pintype "passive"))
      (node (ref "U1") (pin "33") (pinfunction "PB12_33") (pintype "bidirectional"))
    )
    (net (code "44") (name "/PB13") (class "Default")
      (node (ref "P6") (pin "2") (pinfunction "2_2") (pintype "passive"))
      (node (ref "U1") (pin "34") (pinfunction "PB13_34") (pintype "bidirectional"))
    )
    (net (code "45") (name "/PC0") (class "Default")
      (node (ref "P4") (pin "8") (pinfunction "8_8") (pintype "passive"))
      (node (ref "U1") (pin "8") (pinfunction "PC0_8") (pintype "bidirectional"))
    )
    (net (code "46") (name "/PC1") (class "Default")
      (node (ref "P4") (pin "9") (pinfunction "9_9") (pintype "passive"))
      (node (ref "R43") (pin "2") (pinfunction "2_2") (pintype "passive"))
      (node (ref "U1") (pin "9") (pinfunction "PC1_9") (pintype "bidirectional"))
    )
    (net (code "47") (name "/PC2") (class "Default")
      (node (ref "P4") (pin "10") (pinfunction "10_10") (pintype "passive"))
      (node (ref "R41") (pin "2") (pinfunction "2_2") (pintype "passive"))
      (node (ref "U1") (pin "10") (pinfunction "PC2_10") (pintype "bidirectional"))
    )
    (net (code "48") (name "/PC3") (class "Default")
      (node (ref "P4") (pin "11") (pinfunction "11_11") (pintype "passive"))
      (node (ref "R39") (pin "2") (pinfunction "2_2") (pintype "passive"))
      (node (ref "U1") (pin "11") (pinfunction "PC3_11") (pintype "bidirectional"))
    )
    (net (code "49") (name "/PC6") (class "Default")
      (node (ref "P6") (pin "5") (pinfunction "5_5") (pintype "passive"))
      (node (ref "U1") (pin "37") (pinfunction "PC6_37") (pintype "bidirectional"))
      (node (ref "U4") (pin "9") (pinfunction "SDO/SA1_9") (pintype "passive"))
    )
    (net (code "50") (name "/PC7") (class "Default")
      (node (ref "P6") (pin "6") (pinfunction "6_6") (pintype "passive"))
      (node (ref "R30") (pin "2") (pinfunction "2_2") (pintype "passive"))
      (node (ref "U1") (pin "38") (pinfunction "PC7_38") (pintype "bidirectional"))
    )
    (net (code "51") (name "/PC8") (class "Default")
      (node (ref "P6") (pin "7") (pinfunction "7_7") (pintype "passive"))
      (node (ref "R28") (pin "2") (pinfunction "2_2") (pintype "passive"))
      (node (ref "U1") (pin "39") (pinfunction "PC8_39") (pintype "bidirectional"))
    )
    (net (code "52") (name "/PC9") (class "Default")
      (node (ref "P6") (pin "8") (pinfunction "8_8") (pintype "passive"))
      (node (ref "R15") (pin "1") (pinfunction "1_1") (pintype "passive"))
      (node (ref "U1") (pin "40") (pinfunction "PC9_40") (pintype "bidirectional"))
      (node (ref "U4") (pin "11") (pinfunction "SDA/SDI/SDO_11") (pintype "passive"))
      (node (ref "U5") (pin "14") (pinfunction "SDA_14") (pintype "passive"))
    )
    (net (code "53") (name "/PC11") (class "Default")
      (node (ref "P7") (pin "13") (pinfunction "13_13") (pintype "passive"))
      (node (ref "U1") (pin "52") (pinfunction "PC11_52") (pintype "bidirectional"))
      (node (ref "U3") (pin "9") (pinfunction "SDO/SA1_9") (pintype "passive"))
    )
    (net (code "54") (name "/PC13") (class "Default")
      (node (ref "P4") (pin "2") (pinfunction "2_2") (pintype "passive"))
      (node (ref "U1") (pin "2") (pinfunction "PC13-ANTI_TAMP_2") (pintype "bidirectional"))
    )
    (net (code "55") (name "/PC14") (class "Default")
      (node (ref "P4") (pin "3") (pinfunction "3_3") (pintype "passive"))
      (node (ref "R29") (pin "2") (pinfunction "2_2") (pintype "passive"))
      (node (ref "U1") (pin "3") (pinfunction "PC14-OSC32_IN_3") (pintype "bidirectional"))
    )
    (net (code "56") (name "/PC15") (class "Default")
      (node (ref "P4") (pin "4") (pinfunction "4_4") (pintype "passive"))
      (node (ref "R31") (pin "1") (pinfunction "1_1") (pintype "passive"))
      (node (ref "U1") (pin "4") (pinfunction "PC15-OSC32_OUT_4") (pintype "bidirectional"))
    )
    (net (code "57") (name "/PH0") (class "Default")
      (node (ref "P4") (pin "5") (pinfunction "5_5") (pintype "passive"))
      (node (ref "U1") (pin "5") (pinfunction "PH0-OSC_IN_5") (pintype "bidirectional"))
    )
    (net (code "58") (name "/PH1") (class "Default")
      (node (ref "P4") (pin "6") (pinfunction "6_6") (pintype "passive"))
      (node (ref "U1") (pin "6") (pinfunction "PH1-OSC_OUT_6") (pintype "bidirectional"))
    )
    (net (code "59") (name "/SDA2") (class "Default")
      (node (ref "R13") (pin "1") (pinfunction "1_1") (pintype "passive"))
      (node (ref "U2") (pin "11") (pinfunction "SDA/SDI/SDO_11") (pintype "passive"))
      (node (ref "U7") (pin "14") (pinfunction "SDA_14") (pintype "passive"))
      (node (ref "W1") (pin "2") (pinfunction "C2_2") (pintype "passive"))
    )
    (net (code "60") (name "/VBAT") (class "Default")
      (node (ref "P4") (pin "1") (pinfunction "1_1") (pintype "passive"))
      (node (ref "RBat") (pin "1") (pinfunction "1_1") (pintype "passive"))
      (node (ref "U1") (pin "1") (pinfunction "VBAT_1") (pintype "power_in"))
    )
    (net (code "61") (name "/VCAP1") (class "Default")
      (node (ref "P5") (pin "14") (pinfunction "14_14") (pintype "passive"))
      (node (ref "U1") (pin "30") (pinfunction "VCAP1_30") (pintype "power_in"))
    )
    (net (code "62") (name "/VSSA") (class "Default")
      (node (ref "P4") (pin "12") (pinfunction "12_12") (pintype "passive"))
      (node (ref "R32") (pin "1") (pinfunction "1_1") (pintype "passive"))
      (node (ref "U1") (pin "12") (pinfunction "VSSA/VREF-_12") (pintype "power_in"))
    )
    (net (code "63") (name "AGND") (class "Default")
      (node (ref "R24") (pin "1") (pinfunction "1_1") (pintype "passive"))
      (node (ref "R34") (pin "1") (pinfunction "1_1") (pintype "passive"))
      (node (ref "R36") (pin "1") (pinfunction "1_1") (pintype "passive"))
      (node (ref "R38") (pin "1") (pinfunction "1_1") (pintype "passive"))
      (node (ref "R40") (pin "1") (pinfunction "1_1") (pintype "passive"))
      (node (ref "R42") (pin "1") (pinfunction "1_1") (pintype "passive"))
      (node (ref "R44") (pin "1") (pinfunction "1_1") (pintype "passive"))
    )
    (net (code "64") (name "GND") (class "Default")
      (node (ref "B1") (pin "1") (pinfunction "1_1") (pintype "passive"))
      (node (ref "C1") (pin "1") (pinfunction "1_1") (pintype "passive"))
      (node (ref "C10") (pin "1") (pinfunction "1_1") (pintype "passive"))
      (node (ref "C11") (pin "1") (pinfunction "1_1") (pintype "passive"))
      (node (ref "C12") (pin "1") (pinfunction "1_1") (pintype "passive"))
      (node (ref "C13") (pin "1") (pinfunction "1_1") (pintype "passive"))
      (node (ref "C14") (pin "1") (pinfunction "1_1") (pintype "passive"))
      (node (ref "C15") (pin "1") (pinfunction "1_1") (pintype "passive"))
      (node (ref "C16") (pin "1") (pinfunction "1_1") (pintype "passive"))
      (node (ref "C17") (pin "1") (pinfunction "1_1") (pintype "passive"))
      (node (ref "C18") (pin "1") (pinfunction "1_1") (pintype "passive"))
      (node (ref "C2") (pin "1") (pinfunction "1_1") (pintype "passive"))
      (node (ref "C3") (pin "1") (pinfunction "1_1") (pintype "passive"))
      (node (ref "C37") (pin "2") (pinfunction "2_2") (pintype "passive"))
      (node (ref "C38") (pin "1") (pinfunction "1_1") (pintype "passive"))
      (node (ref "C39") (pin "2") (pinfunction "2_2") (pintype "passive"))
      (node (ref "C4") (pin "1") (pinfunction "1_1") (pintype "passive"))
      (node (ref "C40") (pin "1") (pinfunction "1_1") (pintype "passive"))
      (node (ref "C41") (pin "1") (pinfunction "1_1") (pintype "passive"))
      (node (ref "C42") (pin "1") (pinfunction "1_1") (pintype "passive"))
      (node (ref "C43") (pin "1") (pinfunction "1_1") (pintype "passive"))
      (node (ref "C5") (pin "1") (pinfunction "1_1") (pintype "passive"))
      (node (ref "C6") (pin "1") (pinfunction "1_1") (pintype "passive"))
      (node (ref "C7") (pin "1") (pinfunction "1_1") (pintype "passive"))
      (node (ref "C8") (pin "1") (pinfunction "1_1") (pintype "passive"))
      (node (ref "C9") (pin "1") (pinfunction "1_1") (pintype "passive"))
      (node (ref "D3") (pin "2") (pinfunction "K_2") (pintype "passive"))
      (node (ref "D4") (pin "2") (pinfunction "K_2") (pintype "passive"))
      (node (ref "D5") (pin "2") (pinfunction "K_2") (pintype "passive"))
      (node (ref "D6") (pin "2") (pinfunction "K_2") (pintype "passive"))
      (node (ref "P2") (pin "3") (pinfunction "3_3") (pintype "passive"))
      (node (ref "P2") (pin "5") (pinfunction "5_5") (pintype "passive"))
      (node (ref "P2") (pin "9") (pinfunction "9_9") (pintype "passive"))
      (node (ref "P5") (pin "15") (pinfunction "15_15") (pintype "passive"))
      (node (ref "P5") (pin "2") (pinfunction "2_2") (pintype "passive"))
      (node (ref "P6") (pin "15") (pinfunction "15_15") (pintype "passive"))
      (node (ref "P7") (pin "2") (pinfunction "2_2") (pintype "passive"))
      (node (ref "R1") (pin "2") (pinfunction "2_2") (pintype "passive"))
      (node (ref "R2") (pin "2") (pinfunction "2_2") (pintype "passive"))
      (node (ref "R24") (pin "2") (pinfunction "2_2") (pintype "passive"))
      (node (ref "R26") (pin "1") (pinfunction "1_1") (pintype "passive"))
      (node (ref "R3") (pin "2") (pinfunction "2_2") (pintype "passive"))
      (node (ref "R32") (pin "2") (pinfunction "2_2") (pintype "passive"))
      (node (ref "R4") (pin "2") (pinfunction "2_2") (pintype "passive"))
      (node (ref "R5") (pin "2") (pinfunction "2_2") (pintype "passive"))
      (node (ref "R6") (pin "2") (pinfunction "2_2") (pintype "passive"))
      (node (ref "R7") (pin "1") (pinfunction "1_1") (pintype "passive"))
      (node (ref "R8") (pin "1") (pinfunction "1_1") (pintype "passive"))
      (node (ref "R9") (pin "1") (pinfunction "1_1") (pintype "passive"))
      (node (ref "U1") (pin "18") (pinfunction "VSS_18") (pintype "power_in"))
      (node (ref "U1") (pin "31") (pinfunction "VSS_31") (pintype "power_in"))
      (node (ref "U1") (pin "47") (pinfunction "VSS_47") (pintype "power_in"))
      (node (ref "U1") (pin "63") (pinfunction "VSS_63") (pintype "power_in"))
      (node (ref "U10") (pin "3") (pinfunction "K_3") (pintype "passive"))
      (node (ref "U11") (pin "3") (pinfunction "K_3") (pintype "passive"))
      (node (ref "U12") (pin "3") (pinfunction "K_3") (pintype "passive"))
      (node (ref "U13") (pin "3") (pinfunction "K_3") (pintype "passive"))
      (node (ref "U14") (pin "3") (pinfunction "K_3") (pintype "passive"))
      (node (ref "U15") (pin "3") (pinfunction "K_3") (pintype "passive"))
      (node (ref "U2") (pin "12") (pinfunction "Res_12") (pintype "passive"))
      (node (ref "U2") (pin "2") (pinfunction "Res_2") (pintype "passive"))
      (node (ref "U2") (pin "3") (pinfunction "GND_3") (pintype "passive"))
      (node (ref "U3") (pin "12") (pinfunction "Res_12") (pintype "passive"))
      (node (ref "U3") (pin "2") (pinfunction "Res_2") (pintype "passive"))
      (node (ref "U3") (pin "3") (pinfunction "GND_3") (pintype "passive"))
      (node (ref "U4") (pin "12") (pinfunction "Res_12") (pintype "passive"))
      (node (ref "U4") (pin "2") (pinfunction "Res_2") (pintype "passive"))
      (node (ref "U4") (pin "3") (pinfunction "GND_3") (pintype "passive"))
      (node (ref "U5") (pin "6") (pinfunction "GND_6") (pintype "passive"))
      (node (ref "U5") (pin "7") (pinfunction "GND_7") (pintype "passive"))
      (node (ref "U6") (pin "6") (pinfunction "GND_6") (pintype "passive"))
      (node (ref "U6") (pin "7") (pinfunction "GND_7") (pintype "passive"))
      (node (ref "U7") (pin "6") (pinfunction "GND_6") (pintype "passive"))
      (node (ref "U7") (pin "7") (pinfunction "GND_7") (pintype "passive"))
    )
    (net (code "65") (name "Net-(D3-A)") (class "Default")
      (node (ref "D3") (pin "1") (pinfunction "A_1") (pintype "passive"))
      (node (ref "R25") (pin "1") (pinfunction "1_1") (pintype "passive"))
    )
    (net (code "66") (name "Net-(D4-A)") (class "Default")
      (node (ref "D4") (pin "1") (pinfunction "A_1") (pintype "passive"))
      (node (ref "R27") (pin "1") (pinfunction "1_1") (pintype "passive"))
    )
    (net (code "67") (name "Net-(D5-A)") (class "Default")
      (node (ref "D5") (pin "1") (pinfunction "A_1") (pintype "passive"))
      (node (ref "R28") (pin "1") (pinfunction "1_1") (pintype "passive"))
    )
    (net (code "68") (name "Net-(D6-A)") (class "Default")
      (node (ref "D6") (pin "1") (pinfunction "A_1") (pintype "passive"))
      (node (ref "R30") (pin "1") (pinfunction "1_1") (pintype "passive"))
    )
    (net (code "69") (name "Net-(R2-Pad1)") (class "Default")
      (node (ref "R2") (pin "1") (pinfunction "1_1") (pintype "passive"))
      (node (ref "U5") (pin "10") (pinfunction "nc_10") (pintype "passive"))
    )
    (net (code "70") (name "Net-(R4-Pad1)") (class "Default")
      (node (ref "R4") (pin "1") (pinfunction "1_1") (pintype "passive"))
      (node (ref "U6") (pin "10") (pinfunction "nc_10") (pintype "passive"))
    )
    (net (code "71") (name "Net-(R6-Pad1)") (class "Default")
      (node (ref "R6") (pin "1") (pinfunction "1_1") (pintype "passive"))
      (node (ref "U7") (pin "10") (pinfunction "nc_10") (pintype "passive"))
    )
    (net (code "72") (name "Net-(R7-Pad2)") (class "Default")
      (node (ref "R7") (pin "2") (pinfunction "2_2") (pintype "passive"))
      (node (ref "U5") (pin "11") (pinfunction "nc_11") (pintype "passive"))
    )
    (net (code "73") (name "Net-(R8-Pad2)") (class "Default")
      (node (ref "R8") (pin "2") (pinfunction "2_2") (pintype "passive"))
      (node (ref "U6") (pin "11") (pinfunction "nc_11") (pintype "passive"))
    )
    (net (code "74") (name "Net-(R9-Pad2)") (class "Default")
      (node (ref "R9") (pin "2") (pinfunction "2_2") (pintype "passive"))
      (node (ref "U7") (pin "11") (pinfunction "nc_11") (pintype "passive"))
    )
    (net (code "75") (name "Net-(U2-C1)") (class "Default")
      (node (ref "C5") (pin "2") (pinfunction "2_2") (pintype "passive"))
      (node (ref "U2") (pin "4") (pinfunction "C1_4") (pintype "passive"))
    )
    (net (code "76") (name "Net-(U2-SDO_VDD)") (class "Default")
      (node (ref "C1") (pin "2") (pinfunction "2_2") (pintype "passive"))
      (node (ref "C3") (pin "2") (pinfunction "2_2") (pintype "passive"))
      (node (ref "U2") (pin "5") (pinfunction "SDO_VDD_5") (pintype "passive"))
    )
    (net (code "77") (name "Net-(U3-C1)") (class "Default")
      (node (ref "C6") (pin "2") (pinfunction "2_2") (pintype "passive"))
      (node (ref "U3") (pin "4") (pinfunction "C1_4") (pintype "passive"))
    )
    (net (code "78") (name "Net-(U3-SDO_VDD)") (class "Default")
      (node (ref "C2") (pin "2") (pinfunction "2_2") (pintype "passive"))
      (node (ref "C4") (pin "2") (pinfunction "2_2") (pintype "passive"))
      (node (ref "U3") (pin "5") (pinfunction "SDO_VDD_5") (pintype "passive"))
    )
    (net (code "79") (name "Net-(U4-C1)") (class "Default")
      (node (ref "C9") (pin "2") (pinfunction "2_2") (pintype "passive"))
      (node (ref "U4") (pin "4") (pinfunction "C1_4") (pintype "passive"))
    )
    (net (code "80") (name "Net-(U4-SDO_VDD)") (class "Default")
      (node (ref "C7") (pin "2") (pinfunction "2_2") (pintype "passive"))
      (node (ref "C8") (pin "2") (pinfunction "2_2") (pintype "passive"))
      (node (ref "U4") (pin "5") (pinfunction "SDO_VDD_5") (pintype "passive"))
    )
    (net (code "81") (name "Net-(U5-SC)") (class "Default")
      (node (ref "R1") (pin "1") (pinfunction "1_1") (pintype "passive"))
      (node (ref "U5") (pin "12") (pinfunction "SC_12") (pintype "passive"))
    )
    (net (code "82") (name "Net-(U6-SC)") (class "Default")
      (node (ref "R3") (pin "1") (pinfunction "1_1") (pintype "passive"))
      (node (ref "U6") (pin "12") (pinfunction "SC_12") (pintype "passive"))
    )
    (net (code "83") (name "Net-(U7-SC)") (class "Default")
      (node (ref "R5") (pin "1") (pinfunction "1_1") (pintype "passive"))
      (node (ref "U7") (pin "12") (pinfunction "SC_12") (pintype "passive"))
    )
    (net (code "84") (name "Net-(U10-A)") (class "Default")
      (node (ref "R33") (pin "1") (pinfunction "1_1") (pintype "passive"))
      (node (ref "U10") (pin "1") (pinfunction "A_1") (pintype "passive"))
    )
    (net (code "85") (name "Net-(U11-A)") (class "Default")
      (node (ref "R35") (pin "1") (pinfunction "1_1") (pintype "passive"))
      (node (ref "U11") (pin "1") (pinfunction "A_1") (pintype "passive"))
    )
    (net (code "86") (name "Net-(U12-A)") (class "Default")
      (node (ref "R37") (pin "1") (pinfunction "1_1") (pintype "passive"))
      (node (ref "U12") (pin "1") (pinfunction "A_1") (pintype "passive"))
    )
    (net (code "87") (name "Net-(U13-A)") (class "Default")
      (node (ref "R39") (pin "1") (pinfunction "1_1") (pintype "passive"))
      (node (ref "U13") (pin "1") (pinfunction "A_1") (pintype "passive"))
    )
    (net (code "88") (name "Net-(U14-A)") (class "Default")
      (node (ref "R41") (pin "1") (pinfunction "1_1") (pintype "passive"))
      (node (ref "U14") (pin "1") (pinfunction "A_1") (pintype "passive"))
    )
    (net (code "89") (name "Net-(U15-A)") (class "Default")
      (node (ref "R43") (pin "1") (pinfunction "1_1") (pintype "passive"))
      (node (ref "U15") (pin "1") (pinfunction "A_1") (pintype "passive"))
    )
    (net (code "90") (name "Net-(X1-OSC1)") (class "Default")
      (node (ref "C37") (pin "1") (pinfunction "1_1") (pintype "passive"))
      (node (ref "R29") (pin "1") (pinfunction "1_1") (pintype "passive"))
      (node (ref "X1") (pin "1") (pinfunction "OSC1_1") (pintype "passive"))
    )
    (net (code "91") (name "Net-(X1-OSC2)") (class "Default")
      (node (ref "C39") (pin "1") (pinfunction "1_1") (pintype "passive"))
      (node (ref "R31") (pin "2") (pinfunction "2_2") (pintype "passive"))
      (node (ref "X1") (pin "2") (pinfunction "OSC2_2") (pintype "passive"))
    )
    (net (code "92") (name "VDD") (class "Default")
      (node (ref "C10") (pin "2") (pinfunction "2_2") (pintype "passive"))
      (node (ref "C11") (pin "2") (pinfunction "2_2") (pintype "passive"))
      (node (ref "C12") (pin "2") (pinfunction "2_2") (pintype "passive"))
      (node (ref "C13") (pin "2") (pinfunction "2_2") (pintype "passive"))
      (node (ref "C14") (pin "2") (pinfunction "2_2") (pintype "passive"))
      (node (ref "C15") (pin "2") (pinfunction "2_2") (pintype "passive"))
      (node (ref "C16") (pin "2") (pinfunction "2_2") (pintype "passive"))
      (node (ref "C17") (pin "2") (pinfunction "2_2") (pintype "passive"))
      (node (ref "C18") (pin "2") (pinfunction "2_2") (pintype "passive"))
      (node (ref "C40") (pin "2") (pinfunction "2_2") (pintype "passive"))
      (node (ref "C41") (pin "2") (pinfunction "2_2") (pintype "passive"))
      (node (ref "C42") (pin "2") (pinfunction "2_2") (pintype "passive"))
      (node (ref "C43") (pin "2") (pinfunction "2_2") (pintype "passive"))
      (node (ref "P2") (pin "1") (pinfunction "1_1") (pintype "passive"))
      (node (ref "P4") (pin "13") (pinfunction "13_13") (pintype "passive"))
      (node (ref "P5") (pin "16") (pinfunction "16_16") (pintype "passive"))
      (node (ref "P5") (pin "3") (pinfunction "3_3") (pintype "passive"))
      (node (ref "P6") (pin "16") (pinfunction "16_16") (pintype "passive"))
      (node (ref "P7") (pin "1") (pinfunction "1_1") (pintype "passive"))
      (node (ref "R10") (pin "2") (pinfunction "2_2") (pintype "passive"))
      (node (ref "R11") (pin "2") (pinfunction "2_2") (pintype "passive"))
      (node (ref "R12") (pin "2") (pinfunction "2_2") (pintype "passive"))
      (node (ref "R13") (pin "2") (pinfunction "2_2") (pintype "passive"))
      (node (ref "R14") (pin "2") (pinfunction "2_2") (pintype "passive"))
      (node (ref "R15") (pin "2") (pinfunction "2_2") (pintype "passive"))
      (node (ref "R3.3V") (pin "2") (pinfunction "2_2") (pintype "passive"))
      (node (ref "RBat") (pin "2") (pinfunction "2_2") (pintype "passive"))
      (node (ref "U1") (pin "13") (pinfunction "VDDA/VREF+_13") (pintype "power_in"))
      (node (ref "U1") (pin "19") (pinfunction "VDD_19") (pintype "power_in"))
      (node (ref "U1") (pin "32") (pinfunction "VDD_32") (pintype "power_in"))
      (node (ref "U1") (pin "48") (pinfunction "VDD_48") (pintype "power_in"))
      (node (ref "U1") (pin "64") (pinfunction "VDD_64") (pintype "power_in"))
      (node (ref "U2") (pin "10") (pinfunction "SC_10") (pintype "passive"))
      (node (ref "U2") (pin "6") (pinfunction "VDD_IO_6") (pintype "passive"))
      (node (ref "U3") (pin "10") (pinfunction "SC_10") (pintype "passive"))
      (node (ref "U3") (pin "6") (pinfunction "VDD_IO_6") (pintype "passive"))
      (node (ref "U4") (pin "10") (pinfunction "SC_10") (pintype "passive"))
      (node (ref "U4") (pin "6") (pinfunction "VDD_IO_6") (pintype "passive"))
      (node (ref "U5") (pin "5") (pinfunction "VDDIO_5") (pintype "passive"))
      (node (ref "U5") (pin "8") (pinfunction "VDD_8") (pintype "passive"))
      (node (ref "U6") (pin "5") (pinfunction "VDDIO_5") (pintype "passive"))
      (node (ref "U6") (pin "8") (pinfunction "VDD_8") (pintype "passive"))
      (node (ref "U7") (pin "5") (pinfunction "VDDIO_5") (pintype "passive"))
      (node (ref "U7") (pin "8") (pinfunction "VDD_8") (pintype "passive"))
    )
    (net (code "93") (name "Vout3V") (class "Default")
      (node (ref "R3.3V") (pin "1") (pinfunction "1_1") (pintype "passive"))
    )
    (net (code "94") (name "Vout5V") (class "Default")
      (node (ref "U10") (pin "5") (pinfunction "C_5") (pintype "passive"))
      (node (ref "U11") (pin "5") (pinfunction "C_5") (pintype "passive"))
      (node (ref "U12") (pin "5") (pinfunction "C_5") (pintype "passive"))
      (node (ref "U13") (pin "5") (pinfunction "C_5") (pintype "passive"))
      (node (ref "U14") (pin "5") (pinfunction "C_5") (pintype "passive"))
      (node (ref "U15") (pin "5") (pinfunction "C_5") (pintype "passive"))
    )
    (net (code "95") (name "unconnected-(P2-Pad7)") (class "Default")
      (node (ref "P2") (pin "7") (pinfunction "7_7") (pintype "passive"))
    )
    (net (code "96") (name "unconnected-(P2-Pad8)") (class "Default")
      (node (ref "P2") (pin "8") (pinfunction "8_8") (pintype "passive"))
    )
    (net (code "97") (name "unconnected-(U5-SCx-Pad3)") (class "Default")
      (node (ref "U5") (pin "3") (pinfunction "SCx_3") (pintype "passive"))
    )
    (net (code "98") (name "unconnected-(U5-SDx-Pad2)") (class "Default")
      (node (ref "U5") (pin "2") (pinfunction "SDx_2") (pintype "passive"))
    )
    (net (code "99") (name "unconnected-(U6-SCx-Pad3)") (class "Default")
      (node (ref "U6") (pin "3") (pinfunction "SCx_3") (pintype "passive"))
    )
    (net (code "100") (name "unconnected-(U6-SDx-Pad2)") (class "Default")
      (node (ref "U6") (pin "2") (pinfunction "SDx_2") (pintype "passive"))
    )
    (net (code "101") (name "unconnected-(U7-SCx-Pad3)") (class "Default")
      (node (ref "U7") (pin "3") (pinfunction "SCx_3") (pintype "passive"))
    )
    (net (code "102") (name "unconnected-(U7-SDx-Pad2)") (class "Default")
      (node (ref "U7") (pin "2") (pinfunction "SDx_2") (pintype "passive"))
    )
    (net (code "103") (name "unconnected-(U10-B-Pad6)") (class "Default")
      (node (ref "U10") (pin "6") (pinfunction "B_6") (pintype "passive"))
    )
    (net (code "104") (name "unconnected-(U11-B-Pad6)") (class "Default")
      (node (ref "U11") (pin "6") (pinfunction "B_6") (pintype "passive"))
    )
    (net (code "105") (name "unconnected-(U12-B-Pad6)") (class "Default")
      (node (ref "U12") (pin "6") (pinfunction "B_6") (pintype "passive"))
    )
    (net (code "106") (name "unconnected-(U13-B-Pad6)") (class "Default")
      (node (ref "U13") (pin "6") (pinfunction "B_6") (pintype "passive"))
    )
    (net (code "107") (name "unconnected-(U14-B-Pad6)") (class "Default")
      (node (ref "U14") (pin "6") (pinfunction "B_6") (pintype "passive"))
    )
    (net (code "108") (name "unconnected-(U15-B-Pad6)") (class "Default")
      (node (ref "U15") (pin "6") (pinfunction "B_6") (pintype "passive"))
    )
  )
)
